# untitled.net
KiCad netlist of a schematic drawn in EAGLE
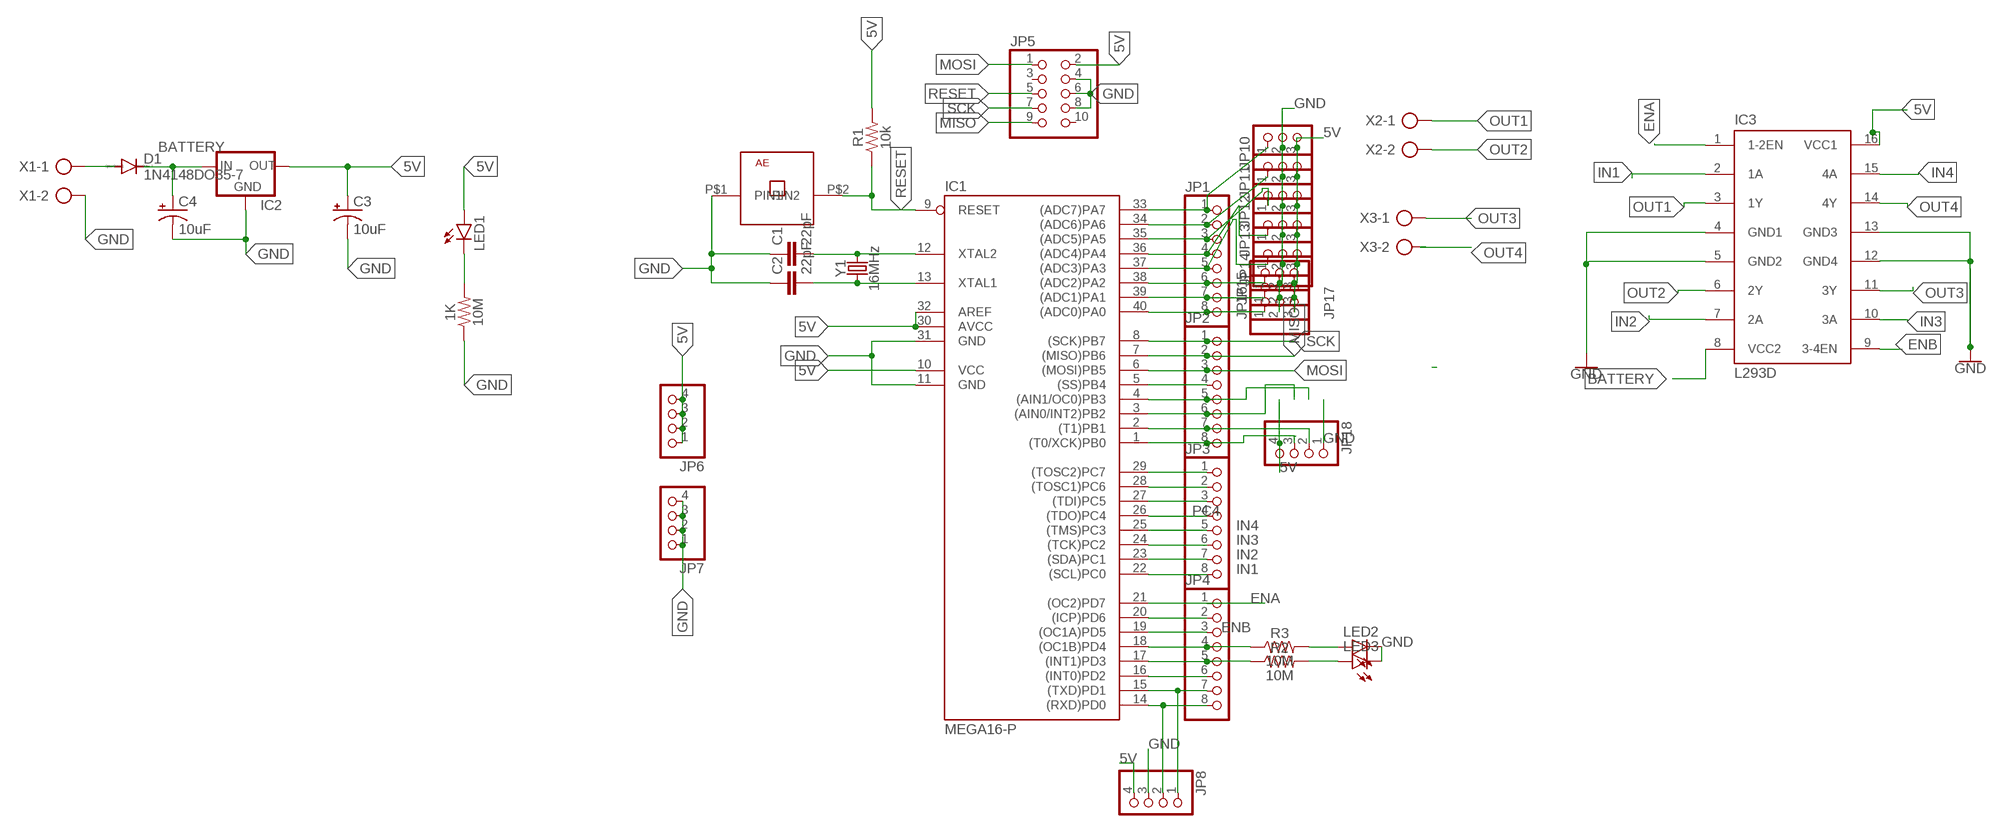
[diagram p0: schematic, sheet 1]

(export (version "E")
  (design (tool "Eeschema 10.0.6"))
  (components
    (comp (ref "1K")
      (value "10M")
      (footprint "eagle-import:AXIAL-0.3")
      (libsource (lib "eagle-import") (part "10MOHM-HORIZ-1/4W-5%"))
    )
    (comp (ref "C1")
      (value "22pF")
      (footprint "eagle-import:CAP-PTH-2.54")
      (libsource (lib "eagle-import") (part "22PF-PTH-2.54MM-200V-5%"))
    )
    (comp (ref "C2")
      (value "22pF")
      (footprint "eagle-import:CAP-PTH-2.54")
      (libsource (lib "eagle-import") (part "22PF-PTH-2.54MM-200V-5%"))
    )
    (comp (ref "C3")
      (value "10uF")
      (footprint "eagle-import:CPOL-RADIAL-2.5MM-5MM")
      (libsource (lib "eagle-import") (part "10UF-POLAR-RADIAL-2.5MM-25V-20%"))
    )
    (comp (ref "C4")
      (value "10uF")
      (footprint "eagle-import:CPOL-RADIAL-2.5MM-5MM")
      (libsource (lib "eagle-import") (part "10UF-POLAR-RADIAL-2.5MM-25V-20%"))
    )
    (comp (ref "D1")
      (value "1N4148DO35-7")
      (footprint "eagle-import:DO35-7")
      (libsource (lib "eagle-import") (part "1N4148DO35-7"))
    )
    (comp (ref "IC1")
      (value "MEGA16-P")
      (footprint "eagle-import:DIL40")
      (fields (field (name "MPN") "ATMEGA16-16PU"))
      (libsource (lib "eagle-import") (part "MEGA16-P"))
    )
    (comp (ref "IC2")
      (value "78XXS")
      (footprint "eagle-import:78XXS")
      (libsource (lib "eagle-import") (part "78XXS"))
    )
    (comp (ref "IC3")
      (value "L293D")
      (footprint "eagle-import:DIL16")
      (libsource (lib "eagle-import") (part "L293D"))
    )
    (comp (ref "JP1")
      (value "PINHD-1X8")
      (footprint "eagle-import:1X08")
      (libsource (lib "eagle-import") (part "PINHD-1X8"))
    )
    (comp (ref "JP2")
      (value "PINHD-1X8")
      (footprint "eagle-import:1X08")
      (libsource (lib "eagle-import") (part "PINHD-1X8"))
    )
    (comp (ref "JP3")
      (value "PINHD-1X8")
      (footprint "eagle-import:1X08")
      (libsource (lib "eagle-import") (part "PINHD-1X8"))
    )
    (comp (ref "JP4")
      (value "PINHD-1X8")
      (footprint "eagle-import:1X08")
      (libsource (lib "eagle-import") (part "PINHD-1X8"))
    )
    (comp (ref "JP5")
      (value "PINHD-2X5")
      (footprint "eagle-import:2X05")
      (libsource (lib "eagle-import") (part "PINHD-2X5"))
    )
    (comp (ref "JP6")
      (value "PINHD-1X4")
      (footprint "eagle-import:1X04")
      (libsource (lib "eagle-import") (part "PINHD-1X4"))
    )
    (comp (ref "JP7")
      (value "PINHD-1X4")
      (footprint "eagle-import:1X04")
      (libsource (lib "eagle-import") (part "PINHD-1X4"))
    )
    (comp (ref "JP8")
      (value "PINHD-1X4")
      (footprint "eagle-import:1X04")
      (libsource (lib "eagle-import") (part "PINHD-1X4"))
    )
    (comp (ref "JP10")
      (value "PINHD-1X3")
      (footprint "eagle-import:1X03")
      (libsource (lib "eagle-import") (part "PINHD-1X3"))
    )
    (comp (ref "JP11")
      (value "PINHD-1X3")
      (footprint "eagle-import:1X03")
      (libsource (lib "eagle-import") (part "PINHD-1X3"))
    )
    (comp (ref "JP12")
      (value "PINHD-1X3")
      (footprint "eagle-import:1X03")
      (libsource (lib "eagle-import") (part "PINHD-1X3"))
    )
    (comp (ref "JP13")
      (value "PINHD-1X3")
      (footprint "eagle-import:1X03")
      (libsource (lib "eagle-import") (part "PINHD-1X3"))
    )
    (comp (ref "JP14")
      (value "PINHD-1X3")
      (footprint "eagle-import:1X03")
      (libsource (lib "eagle-import") (part "PINHD-1X3"))
    )
    (comp (ref "JP15")
      (value "PINHD-1X3")
      (footprint "eagle-import:1X03")
      (libsource (lib "eagle-import") (part "PINHD-1X3"))
    )
    (comp (ref "JP16")
      (value "PINHD-1X3")
      (footprint "eagle-import:1X03")
      (libsource (lib "eagle-import") (part "PINHD-1X3"))
    )
    (comp (ref "JP17")
      (value "PINHD-1X3")
      (footprint "eagle-import:1X03")
      (libsource (lib "eagle-import") (part "PINHD-1X3"))
    )
    (comp (ref "JP18")
      (value "PINHD-1X4")
      (footprint "eagle-import:1X04")
      (libsource (lib "eagle-import") (part "PINHD-1X4"))
    )
    (comp (ref "LED1")
      (value "LED3MM")
      (footprint "eagle-import:LED3MM")
      (libsource (lib "eagle-import") (part "LED3MM"))
    )
    (comp (ref "LED2")
      (value "LED3MM")
      (footprint "eagle-import:LED3MM")
      (libsource (lib "eagle-import") (part "LED3MM"))
    )
    (comp (ref "LED3")
      (value "LED3MM")
      (footprint "eagle-import:LED3MM")
      (libsource (lib "eagle-import") (part "LED3MM"))
    )
    (comp (ref "R1")
      (value "10k")
      (footprint "eagle-import:AXIAL-0.3")
      (libsource (lib "eagle-import") (part "10MOHM-HORIZ-1/4W-5%"))
    )
    (comp (ref "R2")
      (value "10M")
      (footprint "eagle-import:AXIAL-0.3")
      (libsource (lib "eagle-import") (part "10MOHM-HORIZ-1/4W-5%"))
    )
    (comp (ref "R3")
      (value "10M")
      (footprint "eagle-import:AXIAL-0.3")
      (libsource (lib "eagle-import") (part "10MOHM-HORIZ-1/4W-5%"))
    )
    (comp (ref "U$1")
      (value "PUSHBUTTON-AE")
      (footprint "eagle-import:PUSHBUTTON-AE")
      (libsource (lib "eagle-import") (part "PUSHBUTTON-AE"))
    )
    (comp (ref "X1")
      (value "AK500/2-H")
      (footprint "eagle-import:AK500_2-H")
      (libsource (lib "eagle-import") (part "AK500/2-H"))
    )
    (comp (ref "X2")
      (value "AK500/2-H")
      (footprint "eagle-import:AK500_2-H")
      (libsource (lib "eagle-import") (part "con-ptr500_181_AK500/2-H"))
    )
    (comp (ref "X3")
      (value "AK500/2-H")
      (footprint "eagle-import:AK500_2-H")
      (libsource (lib "eagle-import") (part "con-ptr500_181_AK500/2-H"))
    )
    (comp (ref "Y1")
      (value "16MHz")
      (footprint "eagle-import:HC49US")
      (libsource (lib "eagle-import") (part "CRYSTAL-16MHZPTH-HC49US"))
    )
  )
  (nets
    (net (code "1") (name "/PC4") (class "Default")
      (node (ref "IC1") (pin "26") (pinfunction "(TDO)PC4_26") (pintype "bidirectional"))
      (node (ref "JP3") (pin "4") (pinfunction "4_4") (pintype "passive"))
    )
    (net (code "2") (name "5V") (class "Default")
      (node (ref "C3") (pin "1") (pinfunction "+_1") (pintype "passive"))
      (node (ref "IC1") (pin "10") (pinfunction "VCC_10") (pintype "power_in"))
      (node (ref "IC1") (pin "30") (pinfunction "AVCC_30") (pintype "power_in"))
      (node (ref "IC1") (pin "32") (pinfunction "AREF_32") (pintype "passive"))
      (node (ref "IC2") (pin "OUT") (pinfunction "OUT_OUT") (pintype "passive"))
      (node (ref "IC3") (pin "16") (pinfunction "VCC1_16") (pintype "power_in"))
      (node (ref "JP10") (pin "3") (pinfunction "3_3") (pintype "passive"))
      (node (ref "JP11") (pin "3") (pinfunction "3_3") (pintype "passive"))
      (node (ref "JP12") (pin "3") (pinfunction "3_3") (pintype "passive"))
      (node (ref "JP13") (pin "3") (pinfunction "3_3") (pintype "passive"))
      (node (ref "JP14") (pin "3") (pinfunction "3_3") (pintype "passive"))
      (node (ref "JP15") (pin "3") (pinfunction "3_3") (pintype "passive"))
      (node (ref "JP16") (pin "3") (pinfunction "3_3") (pintype "passive"))
      (node (ref "JP17") (pin "3") (pinfunction "3_3") (pintype "passive"))
      (node (ref "JP18") (pin "4") (pinfunction "4_4") (pintype "passive"))
      (node (ref "JP5") (pin "2") (pinfunction "2_2") (pintype "passive"))
      (node (ref "JP6") (pin "1") (pinfunction "1_1") (pintype "passive"))
      (node (ref "JP6") (pin "2") (pinfunction "2_2") (pintype "passive"))
      (node (ref "JP6") (pin "3") (pinfunction "3_3") (pintype "passive"))
      (node (ref "JP6") (pin "4") (pinfunction "4_4") (pintype "passive"))
      (node (ref "JP8") (pin "4") (pinfunction "4_4") (pintype "passive"))
      (node (ref "LED1") (pin "A") (pinfunction "A_A") (pintype "passive"))
      (node (ref "R1") (pin "P$2") (pinfunction "2_P$2") (pintype "passive"))
    )
    (net (code "3") (name "BATTERY") (class "Default")
      (node (ref "C4") (pin "1") (pinfunction "+_1") (pintype "passive"))
      (node (ref "D1") (pin "C") (pinfunction "C_C") (pintype "passive"))
      (node (ref "IC2") (pin "IN") (pinfunction "IN_IN") (pintype "input"))
      (node (ref "IC3") (pin "8") (pinfunction "VCC2_8") (pintype "power_in"))
    )
    (net (code "4") (name "ENA") (class "Default")
      (node (ref "IC1") (pin "21") (pinfunction "(OC2)PD7_21") (pintype "bidirectional"))
      (node (ref "IC3") (pin "1") (pinfunction "1-2EN_1") (pintype "input"))
      (node (ref "JP4") (pin "1") (pinfunction "1_1") (pintype "passive"))
    )
    (net (code "5") (name "ENB") (class "Default")
      (node (ref "IC1") (pin "19") (pinfunction "(OC1A)PD5_19") (pintype "bidirectional"))
      (node (ref "IC3") (pin "9") (pinfunction "3-4EN_9") (pintype "input"))
      (node (ref "JP4") (pin "3") (pinfunction "3_3") (pintype "passive"))
    )
    (net (code "6") (name "GND") (class "Default")
      (node (ref "1K") (pin "P$1") (pinfunction "1_P$1") (pintype "passive"))
      (node (ref "C1") (pin "1") (pinfunction "1_1") (pintype "passive"))
      (node (ref "C2") (pin "1") (pinfunction "1_1") (pintype "passive"))
      (node (ref "C3") (pin "2") (pinfunction "-_2") (pintype "passive"))
      (node (ref "C4") (pin "2") (pinfunction "-_2") (pintype "passive"))
      (node (ref "IC1") (pin "11") (pinfunction "GND_11") (pintype "power_in"))
      (node (ref "IC1") (pin "31") (pinfunction "GND_31") (pintype "power_in"))
      (node (ref "IC2") (pin "GND") (pinfunction "GND_GND") (pintype "input"))
      (node (ref "IC3") (pin "12") (pinfunction "GND4_12") (pintype "power_in"))
      (node (ref "IC3") (pin "13") (pinfunction "GND3_13") (pintype "power_in"))
      (node (ref "IC3") (pin "4") (pinfunction "GND1_4") (pintype "power_in"))
      (node (ref "IC3") (pin "5") (pinfunction "GND2_5") (pintype "power_in"))
      (node (ref "JP10") (pin "2") (pinfunction "2_2") (pintype "passive"))
      (node (ref "JP11") (pin "2") (pinfunction "2_2") (pintype "passive"))
      (node (ref "JP12") (pin "2") (pinfunction "2_2") (pintype "passive"))
      (node (ref "JP13") (pin "2") (pinfunction "2_2") (pintype "passive"))
      (node (ref "JP14") (pin "2") (pinfunction "2_2") (pintype "passive"))
      (node (ref "JP15") (pin "2") (pinfunction "2_2") (pintype "passive"))
      (node (ref "JP16") (pin "2") (pinfunction "2_2") (pintype "passive"))
      (node (ref "JP17") (pin "2") (pinfunction "2_2") (pintype "passive"))
      (node (ref "JP18") (pin "1") (pinfunction "1_1") (pintype "passive"))
      (node (ref "JP5") (pin "4") (pinfunction "4_4") (pintype "passive"))
      (node (ref "JP5") (pin "6") (pinfunction "6_6") (pintype "passive"))
      (node (ref "JP5") (pin "8") (pinfunction "8_8") (pintype "passive"))
      (node (ref "JP7") (pin "1") (pinfunction "1_1") (pintype "passive"))
      (node (ref "JP7") (pin "2") (pinfunction "2_2") (pintype "passive"))
      (node (ref "JP7") (pin "3") (pinfunction "3_3") (pintype "passive"))
      (node (ref "JP7") (pin "4") (pinfunction "4_4") (pintype "passive"))
      (node (ref "JP8") (pin "3") (pinfunction "3_3") (pintype "passive"))
      (node (ref "LED2") (pin "K") (pinfunction "C_K") (pintype "passive"))
      (node (ref "LED3") (pin "K") (pinfunction "C_K") (pintype "passive"))
      (node (ref "U$1") (pin "P$1") (pinfunction "PIN1_P$1") (pintype "bidirectional"))
      (node (ref "X1") (pin "2") (pinfunction "KL_2") (pintype "passive"))
    )
    (net (code "7") (name "IN1") (class "Default")
      (node (ref "IC1") (pin "22") (pinfunction "(SCL)PC0_22") (pintype "bidirectional"))
      (node (ref "IC3") (pin "2") (pinfunction "1A_2") (pintype "input"))
      (node (ref "JP3") (pin "8") (pinfunction "8_8") (pintype "passive"))
    )
    (net (code "8") (name "IN2") (class "Default")
      (node (ref "IC1") (pin "23") (pinfunction "(SDA)PC1_23") (pintype "bidirectional"))
      (node (ref "IC3") (pin "7") (pinfunction "2A_7") (pintype "input"))
      (node (ref "JP3") (pin "7") (pinfunction "7_7") (pintype "passive"))
    )
    (net (code "9") (name "IN3") (class "Default")
      (node (ref "IC1") (pin "24") (pinfunction "(TCK)PC2_24") (pintype "bidirectional"))
      (node (ref "IC3") (pin "10") (pinfunction "3A_10") (pintype "input"))
      (node (ref "JP3") (pin "6") (pinfunction "6_6") (pintype "passive"))
    )
    (net (code "10") (name "IN4") (class "Default")
      (node (ref "IC1") (pin "25") (pinfunction "(TMS)PC3_25") (pintype "bidirectional"))
      (node (ref "IC3") (pin "15") (pinfunction "4A_15") (pintype "input"))
      (node (ref "JP3") (pin "5") (pinfunction "5_5") (pintype "passive"))
    )
    (net (code "11") (name "MISO") (class "Default")
      (node (ref "IC1") (pin "7") (pinfunction "(MISO)PB6_7") (pintype "bidirectional"))
      (node (ref "JP2") (pin "2") (pinfunction "2_2") (pintype "passive"))
      (node (ref "JP5") (pin "9") (pinfunction "9_9") (pintype "passive"))
    )
    (net (code "12") (name "MOSI") (class "Default")
      (node (ref "IC1") (pin "6") (pinfunction "(MOSI)PB5_6") (pintype "bidirectional"))
      (node (ref "JP2") (pin "3") (pinfunction "3_3") (pintype "passive"))
      (node (ref "JP5") (pin "1") (pinfunction "1_1") (pintype "passive"))
    )
    (net (code "13") (name "Net-(1K-2)") (class "Default")
      (node (ref "1K") (pin "P$2") (pinfunction "2_P$2") (pintype "passive"))
      (node (ref "LED1") (pin "K") (pinfunction "C_K") (pintype "passive"))
    )
    (net (code "14") (name "Net-(IC1-(ADC0)PA0)") (class "Default")
      (node (ref "IC1") (pin "40") (pinfunction "(ADC0)PA0_40") (pintype "bidirectional"))
      (node (ref "JP1") (pin "8") (pinfunction "8_8") (pintype "passive"))
      (node (ref "JP17") (pin "1") (pinfunction "1_1") (pintype "passive"))
    )
    (net (code "15") (name "Net-(IC1-(ADC1)PA1)") (class "Default")
      (node (ref "IC1") (pin "39") (pinfunction "(ADC1)PA1_39") (pintype "bidirectional"))
      (node (ref "JP1") (pin "7") (pinfunction "7_7") (pintype "passive"))
      (node (ref "JP16") (pin "1") (pinfunction "1_1") (pintype "passive"))
    )
    (net (code "16") (name "Net-(IC1-(ADC2)PA2)") (class "Default")
      (node (ref "IC1") (pin "38") (pinfunction "(ADC2)PA2_38") (pintype "bidirectional"))
      (node (ref "JP1") (pin "6") (pinfunction "6_6") (pintype "passive"))
      (node (ref "JP15") (pin "1") (pinfunction "1_1") (pintype "passive"))
    )
    (net (code "17") (name "Net-(IC1-(ADC3)PA3)") (class "Default")
      (node (ref "IC1") (pin "37") (pinfunction "(ADC3)PA3_37") (pintype "bidirectional"))
      (node (ref "JP1") (pin "5") (pinfunction "5_5") (pintype "passive"))
      (node (ref "JP14") (pin "1") (pinfunction "1_1") (pintype "passive"))
    )
    (net (code "18") (name "Net-(IC1-(ADC4)PA4)") (class "Default")
      (node (ref "IC1") (pin "36") (pinfunction "(ADC4)PA4_36") (pintype "bidirectional"))
      (node (ref "JP1") (pin "4") (pinfunction "4_4") (pintype "passive"))
      (node (ref "JP13") (pin "1") (pinfunction "1_1") (pintype "passive"))
    )
    (net (code "19") (name "Net-(IC1-(ADC5)PA5)") (class "Default")
      (node (ref "IC1") (pin "35") (pinfunction "(ADC5)PA5_35") (pintype "bidirectional"))
      (node (ref "JP1") (pin "3") (pinfunction "3_3") (pintype "passive"))
      (node (ref "JP12") (pin "1") (pinfunction "1_1") (pintype "passive"))
    )
    (net (code "20") (name "Net-(IC1-(ADC6)PA6)") (class "Default")
      (node (ref "IC1") (pin "34") (pinfunction "(ADC6)PA6_34") (pintype "bidirectional"))
      (node (ref "JP1") (pin "2") (pinfunction "2_2") (pintype "passive"))
      (node (ref "JP11") (pin "1") (pinfunction "1_1") (pintype "passive"))
    )
    (net (code "21") (name "Net-(IC1-(ADC7)PA7)") (class "Default")
      (node (ref "IC1") (pin "33") (pinfunction "(ADC7)PA7_33") (pintype "bidirectional"))
      (node (ref "JP1") (pin "1") (pinfunction "1_1") (pintype "passive"))
      (node (ref "JP10") (pin "1") (pinfunction "1_1") (pintype "passive"))
    )
    (net (code "22") (name "Net-(IC1-(AIN0{slash}INT2)PB2)") (class "Default")
      (node (ref "IC1") (pin "3") (pinfunction "(AIN0/INT2)PB2_3") (pintype "bidirectional"))
      (node (ref "JP2") (pin "6") (pinfunction "6_6") (pintype "passive"))
    )
    (net (code "23") (name "Net-(IC1-(AIN1{slash}OC0)PB3)") (class "Default")
      (node (ref "IC1") (pin "4") (pinfunction "(AIN1/OC0)PB3_4") (pintype "bidirectional"))
      (node (ref "JP2") (pin "5") (pinfunction "5_5") (pintype "passive"))
    )
    (net (code "24") (name "Net-(IC1-(ICP)PD6)") (class "Default")
      (node (ref "IC1") (pin "20") (pinfunction "(ICP)PD6_20") (pintype "bidirectional"))
      (node (ref "JP4") (pin "2") (pinfunction "2_2") (pintype "passive"))
    )
    (net (code "25") (name "Net-(IC1-(INT0)PD2)") (class "Default")
      (node (ref "IC1") (pin "16") (pinfunction "(INT0)PD2_16") (pintype "bidirectional"))
      (node (ref "JP4") (pin "6") (pinfunction "6_6") (pintype "passive"))
    )
    (net (code "26") (name "Net-(IC1-(INT1)PD3)") (class "Default")
      (node (ref "IC1") (pin "17") (pinfunction "(INT1)PD3_17") (pintype "bidirectional"))
      (node (ref "JP4") (pin "5") (pinfunction "5_5") (pintype "passive"))
      (node (ref "R2") (pin "P$1") (pinfunction "1_P$1") (pintype "passive"))
    )
    (net (code "27") (name "Net-(IC1-(OC1B)PD4)") (class "Default")
      (node (ref "IC1") (pin "18") (pinfunction "(OC1B)PD4_18") (pintype "bidirectional"))
      (node (ref "JP4") (pin "4") (pinfunction "4_4") (pintype "passive"))
      (node (ref "R3") (pin "P$1") (pinfunction "1_P$1") (pintype "passive"))
    )
    (net (code "28") (name "Net-(IC1-(RXD)PD0)") (class "Default")
      (node (ref "IC1") (pin "14") (pinfunction "(RXD)PD0_14") (pintype "bidirectional"))
      (node (ref "JP4") (pin "8") (pinfunction "8_8") (pintype "passive"))
      (node (ref "JP8") (pin "2") (pinfunction "2_2") (pintype "passive"))
    )
    (net (code "29") (name "Net-(IC1-(SS)PB4)") (class "Default")
      (node (ref "IC1") (pin "5") (pinfunction "(SS)PB4_5") (pintype "bidirectional"))
      (node (ref "JP2") (pin "4") (pinfunction "4_4") (pintype "passive"))
    )
    (net (code "30") (name "Net-(IC1-(T0{slash}XCK)PB0)") (class "Default")
      (node (ref "IC1") (pin "1") (pinfunction "(T0/XCK)PB0_1") (pintype "bidirectional"))
      (node (ref "JP18") (pin "3") (pinfunction "3_3") (pintype "passive"))
      (node (ref "JP2") (pin "8") (pinfunction "8_8") (pintype "passive"))
    )
    (net (code "31") (name "Net-(IC1-(T1)PB1)") (class "Default")
      (node (ref "IC1") (pin "2") (pinfunction "(T1)PB1_2") (pintype "bidirectional"))
      (node (ref "JP18") (pin "2") (pinfunction "2_2") (pintype "passive"))
      (node (ref "JP2") (pin "7") (pinfunction "7_7") (pintype "passive"))
    )
    (net (code "32") (name "Net-(IC1-(TDI)PC5)") (class "Default")
      (node (ref "IC1") (pin "27") (pinfunction "(TDI)PC5_27") (pintype "bidirectional"))
      (node (ref "JP3") (pin "3") (pinfunction "3_3") (pintype "passive"))
    )
    (net (code "33") (name "Net-(IC1-(TOSC1)PC6)") (class "Default")
      (node (ref "IC1") (pin "28") (pinfunction "(TOSC1)PC6_28") (pintype "bidirectional"))
      (node (ref "JP3") (pin "2") (pinfunction "2_2") (pintype "passive"))
    )
    (net (code "34") (name "Net-(IC1-(TOSC2)PC7)") (class "Default")
      (node (ref "IC1") (pin "29") (pinfunction "(TOSC2)PC7_29") (pintype "bidirectional"))
      (node (ref "JP3") (pin "1") (pinfunction "1_1") (pintype "passive"))
    )
    (net (code "35") (name "Net-(IC1-(TXD)PD1)") (class "Default")
      (node (ref "IC1") (pin "15") (pinfunction "(TXD)PD1_15") (pintype "bidirectional"))
      (node (ref "JP4") (pin "7") (pinfunction "7_7") (pintype "passive"))
      (node (ref "JP8") (pin "1") (pinfunction "1_1") (pintype "passive"))
    )
    (net (code "36") (name "Net-(IC1-XTAL1)") (class "Default")
      (node (ref "C2") (pin "2") (pinfunction "2_2") (pintype "passive"))
      (node (ref "IC1") (pin "13") (pinfunction "XTAL1_13") (pintype "bidirectional"))
      (node (ref "Y1") (pin "1") (pinfunction "1_1") (pintype "passive"))
    )
    (net (code "37") (name "Net-(IC1-XTAL2)") (class "Default")
      (node (ref "C1") (pin "2") (pinfunction "2_2") (pintype "passive"))
      (node (ref "IC1") (pin "12") (pinfunction "XTAL2_12") (pintype "bidirectional"))
      (node (ref "Y1") (pin "2") (pinfunction "2_2") (pintype "passive"))
    )
    (net (code "38") (name "Net-(R2-2)") (class "Default")
      (node (ref "LED3") (pin "A") (pinfunction "A_A") (pintype "passive"))
      (node (ref "R2") (pin "P$2") (pinfunction "2_P$2") (pintype "passive"))
    )
    (net (code "39") (name "Net-(R3-2)") (class "Default")
      (node (ref "LED2") (pin "A") (pinfunction "A_A") (pintype "passive"))
      (node (ref "R3") (pin "P$2") (pinfunction "2_P$2") (pintype "passive"))
    )
    (net (code "40") (name "Net-(X1A-KL)") (class "Default")
      (node (ref "D1") (pin "A") (pinfunction "A_A") (pintype "passive"))
      (node (ref "X1") (pin "1") (pinfunction "KL_1") (pintype "passive"))
    )
    (net (code "41") (name "OUT1") (class "Default")
      (node (ref "IC3") (pin "3") (pinfunction "1Y_3") (pintype "output"))
      (node (ref "X2") (pin "1") (pinfunction "KL_1") (pintype "passive"))
    )
    (net (code "42") (name "OUT2") (class "Default")
      (node (ref "IC3") (pin "6") (pinfunction "2Y_6") (pintype "output"))
      (node (ref "X2") (pin "2") (pinfunction "KL_2") (pintype "passive"))
    )
    (net (code "43") (name "OUT3") (class "Default")
      (node (ref "IC3") (pin "11") (pinfunction "3Y_11") (pintype "output"))
      (node (ref "X3") (pin "1") (pinfunction "KL_1") (pintype "passive"))
    )
    (net (code "44") (name "OUT4") (class "Default")
      (node (ref "IC3") (pin "14") (pinfunction "4Y_14") (pintype "output"))
      (node (ref "X3") (pin "2") (pinfunction "KL_2") (pintype "passive"))
    )
    (net (code "45") (name "RESET") (class "Default")
      (node (ref "IC1") (pin "9") (pinfunction "RESET_9") (pintype "input"))
      (node (ref "JP5") (pin "5") (pinfunction "5_5") (pintype "passive"))
      (node (ref "R1") (pin "P$1") (pinfunction "1_P$1") (pintype "passive"))
      (node (ref "U$1") (pin "P$2") (pinfunction "PIN2_P$2") (pintype "bidirectional"))
    )
    (net (code "46") (name "SCK") (class "Default")
      (node (ref "IC1") (pin "8") (pinfunction "(SCK)PB7_8") (pintype "bidirectional"))
      (node (ref "JP2") (pin "1") (pinfunction "1_1") (pintype "passive"))
      (node (ref "JP5") (pin "7") (pinfunction "7_7") (pintype "passive"))
    )
    (net (code "47") (name "unconnected-(JP5-Pad3)") (class "Default")
      (node (ref "JP5") (pin "3") (pinfunction "3_3") (pintype "passive"))
    )
    (net (code "48") (name "unconnected-(JP5-Pad10)") (class "Default")
      (node (ref "JP5") (pin "10") (pinfunction "10_10") (pintype "passive"))
    )
  )
)
